# AL2_Signal_Isolation.net
KiCad netlist of a schematic drawn in Altium Designer
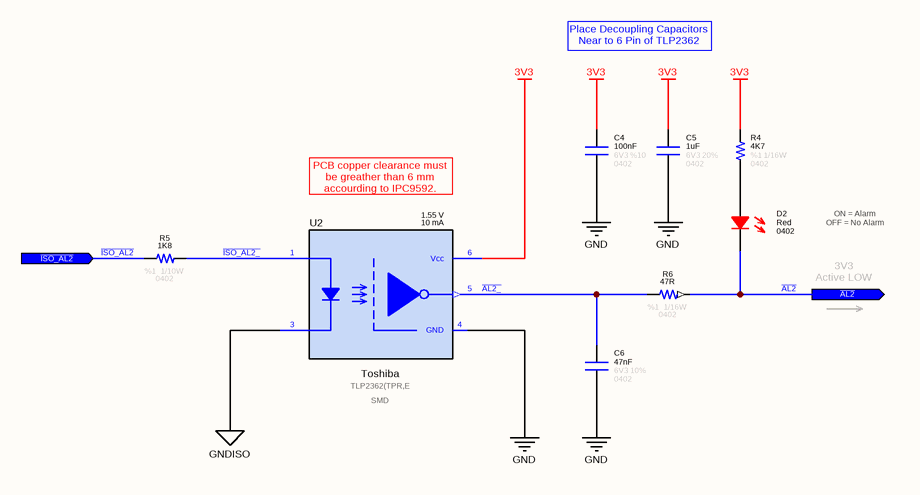
[diagram p0: AL2 Signal Isolation.SchDoc]

(export (version "E")
  (design (tool "Eeschema 10.0.6"))
  (components
    (comp (ref "C4")
      (value "100nF")
      (footprint "CAPACITOR_0402")
      (description "Capacitor - 100nF [0402-6V3] (Ceramic)")
      (fields
        (field (name "MANUFACTURER PART NUMBER") "04026D104KAT4A")
        (field (name "TOLERANCE") "%10")
        (field (name "VOLTAGE") "6V3")
        (field (name "CASE") "0402")
        (field (name "Comment") "Capacitor - 100nF [0402] (Ceramic)")
      )
      (libsource (lib "Akkoyun") (part "Capacitor - 100nF [0402-6V3]"))
    )
    (comp (ref "C5")
      (value "1uF")
      (footprint "CAPACITOR_0402")
      (description "Capacitor (MLCC) - 1uF / 6V3 / 0402")
      (fields
        (field (name "MANUFACTURER PART NUMBER") "GRM153R60J105ME95D")
        (field (name "TOLERANCE") "20%")
        (field (name "CASE") "0402")
        (field (name "VOLTAGE") "6V3")
        (field (name "Comment") "Capacitor - 1uF [0402] (MLCC)")
      )
      (libsource (lib "Akkoyun") (part "Capacitor - 1uF [0402-6V3]"))
    )
    (comp (ref "C6")
      (value "47nF")
      (footprint "CAPACITOR_0402")
      (description "Capacitor (MLCC) - 47nF / 6V3 / 0402")
      (fields
        (field (name "MANUFACTURER PART NUMBER") "04026D473KAT2A")
        (field (name "TOLERANCE") "10%")
        (field (name "CASE") "0402")
        (field (name "VOLTAGE") "6V3")
        (field (name "Comment") "Capacitor - 47nF [0402] (MLCC)")
      )
      (libsource (lib "Akkoyun") (part "Capacitor - 47nF [0402-6V3]"))
    )
    (comp (ref "D2")
      (value "SMD LED (Red)")
      (footprint "LED_0402")
      (description "Standard LEDs - SMD MINI-MOLD ULTRA COMPACT RED")
      (fields
        (field (name "MANUFACTURER PART NUMBER") "SML-P12VTT86R")
        (field (name "CASE") "0402")
        (field (name "COLOR") "Red")
      )
      (libsource (lib "Akkoyun") (part "Diode - LED (0402-Red)"))
    )
    (comp (ref "R4")
      (value "4K7")
      (footprint "RESISTOR_0402")
      (description "Thick Film Resistors - SMD 1/16 W 4.7 KOhm 1%")
      (fields
        (field (name "MANUFACTURER PART NUMBER") "CRCW04024K70FKED")
        (field (name "TOLERANCE") "%1")
        (field (name "CASE") "0402")
        (field (name "POWER") "1/16W")
        (field (name "Comment") "4K7 - 0402 - %1 - 1/16W")
      )
      (libsource (lib "Akkoyun") (part "Resistor - 4K7 [0402]"))
    )
    (comp (ref "R5")
      (value "1K8")
      (footprint "RESISTOR_0402")
      (description "Thick Film Resistors - SMD 1/16 W 1.8 KOhm 1%")
      (fields
        (field (name "MANUFACTURER PART NUMBER") "CRCW04021K80FKED")
        (field (name "TOLERANCE") "%1")
        (field (name "CASE") "0402")
        (field (name "POWER") "1/10W")
        (field (name "Comment") "1K8 - 0402 - %1 - 1/16W")
      )
      (libsource (lib "Akkoyun") (part "Resistor - 1K8 [0402]"))
    )
    (comp (ref "R6")
      (value "47R")
      (footprint "RESISTOR_0402")
      (description "Thick Film Resistors - SMD 1/16 W 47 Ohm 1%")
      (fields
        (field (name "MANUFACTURER PART NUMBER") "CRCW040247R0FKED")
        (field (name "CASE") "0402")
        (field (name "TOLERANCE") "%1")
        (field (name "POWER") "1/16W")
        (field (name "Comment") "47R - 0402 - %1 - 1/16W")
      )
      (libsource (lib "Akkoyun") (part "Resistor - 47R [0402]"))
    )
    (comp (ref "U2")
      (value "TLP2362(TPR,E")
      (footprint "TLP2362")
      (description "High Speed Optocouplers 3750 Vrms 10MBd 4mA 2.7 to 5.5V LED")
      (fields
        (field (name "IF - FORWARD CURRENT") "10 mA")
        (field (name "VF - FORWARD VOLTAGE") "1.55 V")
        (field (name "MANUFACTURER NAME") "Toshiba")
        (field (name "MANUFACTURER PART NUMBER") "TLP2362(TPR,E")
        (field (name "CASE") "SMD")
      )
      (libsource (lib "Akkoyun") (part "IC - TLP2362"))
    )
  )
  (nets
    (net (code "1") (name "/~{AL2_}") (class "Default")
      (node (ref "C6") (pin "2") (pinfunction "2_2") (pintype "passive"))
      (node (ref "R6") (pin "2") (pinfunction "2_2") (pintype "passive"))
      (node (ref "U2") (pin "5") (pinfunction "Output_5") (pintype "output"))
    )
    (net (code "2") (name "/~{AL2}") (class "Default")
      (node (ref "D2") (pin "1") (pinfunction "1_1") (pintype "passive"))
      (node (ref "R6") (pin "1") (pinfunction "1_1") (pintype "output"))
    )
    (net (code "3") (name "/~{ISO_AL2_}") (class "Default")
      (node (ref "R5") (pin "1") (pinfunction "1_1") (pintype "passive"))
      (node (ref "U2") (pin "1") (pinfunction "Anode_1") (pintype "passive"))
    )
    (net (code "4") (name "/~{ISO_AL2}") (class "Default")
      (node (ref "R5") (pin "2") (pinfunction "2_2") (pintype "passive"))
    )
    (net (code "5") (name "3V3") (class "Default")
      (node (ref "C4") (pin "2") (pinfunction "2_2") (pintype "passive"))
      (node (ref "C5") (pin "2") (pinfunction "2_2") (pintype "passive"))
      (node (ref "R4") (pin "2") (pinfunction "2_2") (pintype "passive"))
      (node (ref "U2") (pin "6") (pinfunction "Vcc_6") (pintype "power_in"))
    )
    (net (code "6") (name "GND") (class "Default")
      (node (ref "C4") (pin "1") (pinfunction "1_1") (pintype "passive"))
      (node (ref "C5") (pin "1") (pinfunction "1_1") (pintype "passive"))
      (node (ref "C6") (pin "1") (pinfunction "1_1") (pintype "passive"))
      (node (ref "U2") (pin "4") (pinfunction "GND_4") (pintype "power_in"))
    )
    (net (code "7") (name "GNDISO") (class "Default")
      (node (ref "U2") (pin "3") (pinfunction "Cathode_3") (pintype "passive"))
    )
    (net (code "8") (name "Net-(D2-Pad2)") (class "Default")
      (node (ref "D2") (pin "2") (pinfunction "2_2") (pintype "passive"))
      (node (ref "R4") (pin "1") (pinfunction "1_1") (pintype "passive"))
    )
  )
)
